# SeccionMicrocontrolador.net
KiCad netlist of a schematic drawn in Altium Designer
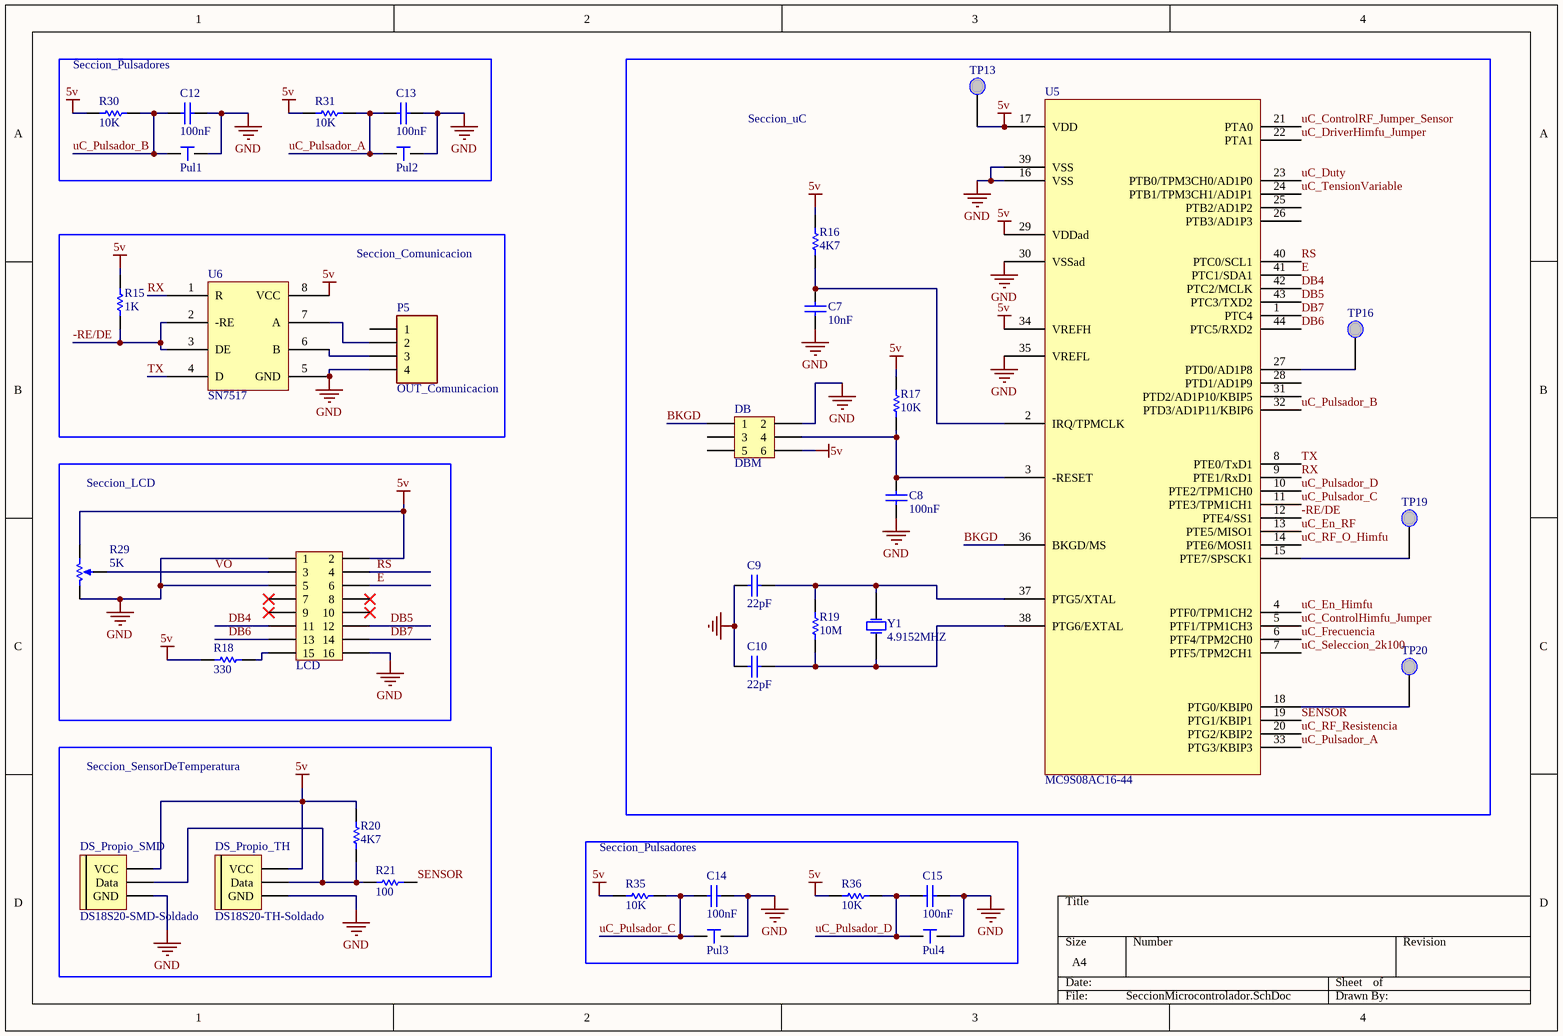
[diagram p0: SeccionMicrocontrolador.SchDoc]

(export (version "E")
  (design (tool "Eeschema 10.0.6"))
  (components
    (comp (ref "C7")
      (value "10nF")
      (footprint "Nahuel_SMD_Body:C_0805")
      (description "CAP CER 10000PF 25V X7R 0805")
      (fields (field (name "PUBLISHER") "Altium Limited"))
      (libsource (lib "Nahuel_SMD_Body") (part "C_10nF"))
    )
    (comp (ref "C8")
      (value "100nF")
      (footprint "Nahuel_SMD_Body:C_0805")
      (description "CAP CER 0.1UF 25V X7R 0805")
      (fields (field (name "PUBLISHER") "Altium Limited"))
      (libsource (lib "Nahuel_SMD_Body") (part "C_100nF"))
    )
    (comp (ref "C9")
      (value "22pF")
      (footprint "Nahuel_SMD_Body:C_0805")
      (description "CAP CER 22PF 50V C0G/NP0 0805")
      (fields (field (name "PUBLISHER") "Altium Limited"))
      (libsource (lib "Nahuel_SMD_Body") (part "C_22pF"))
    )
    (comp (ref "C10")
      (value "22pF")
      (footprint "Nahuel_SMD_Body:C_0805")
      (description "CAP CER 22PF 50V C0G/NP0 0805")
      (fields (field (name "PUBLISHER") "Altium Limited"))
      (libsource (lib "Nahuel_SMD_Body") (part "C_22pF"))
    )
    (comp (ref "C12")
      (value "100nF")
      (footprint "Nahuel_SMD_Body:C_0805")
      (description "CAP CER 0.1UF 25V X7R 0805")
      (fields (field (name "PUBLISHER") "Altium Limited"))
      (libsource (lib "Nahuel_SMD_Body") (part "C_100nF"))
    )
    (comp (ref "C13")
      (value "100nF")
      (footprint "Nahuel_SMD_Body:C_0805")
      (description "CAP CER 0.1UF 25V X7R 0805")
      (fields (field (name "PUBLISHER") "Altium Limited"))
      (libsource (lib "Nahuel_SMD_Body") (part "C_100nF"))
    )
    (comp (ref "C14")
      (value "100nF")
      (footprint "Nahuel_SMD_Body:C_0805")
      (description "CAP CER 0.1UF 25V X7R 0805")
      (fields (field (name "PUBLISHER") "Altium Limited"))
      (libsource (lib "Nahuel_SMD_Body") (part "C_100nF"))
    )
    (comp (ref "C15")
      (value "100nF")
      (footprint "Nahuel_SMD_Body:C_0805")
      (description "CAP CER 0.1UF 25V X7R 0805")
      (fields (field (name "PUBLISHER") "Altium Limited"))
      (libsource (lib "Nahuel_SMD_Body") (part "C_100nF"))
    )
    (comp (ref "DB")
      (value "DBM")
      (footprint "Nahuel_TH_BODY:DBM")
      (description "CONN HEADER VERT 6POS 2.54MM")
      (fields (field (name "PUBLISHER") "Altium Limited"))
      (libsource (lib "Nahuel_TH_BODY") (part "DBM"))
    )
    (comp (ref "DS_Propio_SMD")
      (value "DS18S20-SMD-Soldado")
      (footprint "Nahuel_SMD_Body:SOIC8")
      (description "SENSOR DIGITAL -55C-125C 8SOIC")
      (fields (field (name "PUBLISHER") "Altium Limited"))
      (libsource (lib "Nahuel_SMD_Body") (part "DS18S20-SMD-Soldado"))
    )
    (comp (ref "DS_Propio_TH")
      (value "DS18S20-TH-Soldado")
      (footprint "Nahuel_TH_BODY:TO92")
      (description "Temperature Sensor Digital, Local -55°C ~ 125°C 8 b TO-92-3")
      (fields (field (name "PUBLISHER") "Altium Limited"))
      (libsource (lib "Nahuel_TH_BODY") (part "DS18S20-TH-Soldado"))
    )
    (comp (ref "LCD")
      (value "LCD_Pines")
      (footprint "Nahuel_TH_BODY:LCD_Pines")
      (description "CONN HEADER VERT 16POS 2.54MM")
      (fields (field (name "PUBLISHER") "Altium Limited"))
      (libsource (lib "Nahuel_TH_BODY") (part "LCD_Pines"))
    )
    (comp (ref "P5")
      (value "OUT_Comunicacion")
      (footprint "B4B-XH-A_3D")
      (description "CONN HEADER XH TOP 4POS 2.5MM")
      (fields (field (name "PUBLISHER") "Altium Limited"))
      (libsource (lib "Nahuel_Connectors_BODY") (part "JST_2.5_4"))
    )
    (comp (ref "Pul1")
      (value "PinesParaPulsador")
      (footprint "Nahuel_TH_BODY:Jumper-Simple")
      (description "CONN HEADER 2 POS 2.54")
      (fields (field (name "PUBLISHER") "Altium Limited"))
      (libsource (lib "Nahuel_TH_BODY") (part "PinesParaPulsador"))
    )
    (comp (ref "Pul2")
      (value "PinesParaPulsador")
      (footprint "Nahuel_TH_BODY:Jumper-Simple")
      (description "CONN HEADER 2 POS 2.54")
      (fields (field (name "PUBLISHER") "Altium Limited"))
      (libsource (lib "Nahuel_TH_BODY") (part "PinesParaPulsador"))
    )
    (comp (ref "Pul3")
      (value "PinesParaPulsador")
      (footprint "Nahuel_TH_BODY:Jumper-Simple")
      (description "CONN HEADER 2 POS 2.54")
      (fields (field (name "PUBLISHER") "Altium Limited"))
      (libsource (lib "Nahuel_TH_BODY") (part "PinesParaPulsador"))
    )
    (comp (ref "Pul4")
      (value "PinesParaPulsador")
      (footprint "Nahuel_TH_BODY:Jumper-Simple")
      (description "CONN HEADER 2 POS 2.54")
      (fields (field (name "PUBLISHER") "Altium Limited"))
      (libsource (lib "Nahuel_TH_BODY") (part "PinesParaPulsador"))
    )
    (comp (ref "R15")
      (value "1K")
      (footprint "Nahuel_SMD_Body:R_0805")
      (description "RES SMD 1K OHM 1% 1/8W 0805")
      (fields (field (name "PUBLISHER") "Altium Limited"))
      (libsource (lib "Nahuel_SMD_Body") (part "R_1k"))
    )
    (comp (ref "R16")
      (value "4K7")
      (footprint "Nahuel_SMD_Body:R_0805")
      (description "RES SMD 4K7 OHM 1% 1/8W 0805")
      (fields (field (name "PUBLISHER") "Altium Limited"))
      (libsource (lib "Nahuel_SMD_Body") (part "R_4k7"))
    )
    (comp (ref "R17")
      (value "10K")
      (footprint "Nahuel_SMD_Body:R_0805")
      (description "RES SMD 10K OHM 1% 1/8W 0805")
      (fields (field (name "PUBLISHER") "Altium Limited"))
      (libsource (lib "Nahuel_SMD_Body") (part "R_10k"))
    )
    (comp (ref "R18")
      (value "330")
      (footprint "Nahuel_SMD_Body:R_0805")
      (description "RES SMD 330 OHM 1% 1/8W 0805")
      (fields (field (name "PUBLISHER") "Altium Limited"))
      (libsource (lib "Nahuel_SMD_Body") (part "R_330"))
    )
    (comp (ref "R19")
      (value "10M")
      (footprint "Nahuel_SMD_Body:R_0805")
      (description "RES SMD 10M OHM 5% 1/8W 0805")
      (fields (field (name "PUBLISHER") "Altium Limited"))
      (libsource (lib "Nahuel_SMD_Body") (part "R_10M"))
    )
    (comp (ref "R20")
      (value "4K7")
      (footprint "Nahuel_SMD_Body:R_0805")
      (description "RES SMD 4K7 OHM 1% 1/8W 0805")
      (fields (field (name "PUBLISHER") "Altium Limited"))
      (libsource (lib "Nahuel_SMD_Body") (part "R_4k7"))
    )
    (comp (ref "R21")
      (value "100")
      (footprint "Nahuel_SMD_Body:R_0805")
      (description "RES SMD 100 OHM 1% 1/8W 0805")
      (fields (field (name "PUBLISHER") "Altium Limited"))
      (libsource (lib "Nahuel_SMD_Body") (part "R_100"))
    )
    (comp (ref "R29")
      (value "5K")
      (footprint "Nahuel_SMD_Body:Preset_SMD")
      (description "TRIMMER 5K OHM 0.5W GW TOP ADJ")
      (fields (field (name "PUBLISHER") "Altium Limited"))
      (libsource (lib "Nahuel_SMD_Body") (part "Preset_5k_SMD"))
    )
    (comp (ref "R30")
      (value "10K")
      (footprint "Nahuel_SMD_Body:R_0805")
      (description "RES SMD 10K OHM 1% 1/8W 0805")
      (fields (field (name "PUBLISHER") "Altium Limited"))
      (libsource (lib "Nahuel_SMD_Body") (part "R_10k"))
    )
    (comp (ref "R31")
      (value "10K")
      (footprint "Nahuel_SMD_Body:R_0805")
      (description "RES SMD 10K OHM 1% 1/8W 0805")
      (fields (field (name "PUBLISHER") "Altium Limited"))
      (libsource (lib "Nahuel_SMD_Body") (part "R_10k"))
    )
    (comp (ref "R35")
      (value "10K")
      (footprint "Nahuel_SMD_Body:R_0805")
      (description "RES SMD 10K OHM 1% 1/8W 0805")
      (fields (field (name "PUBLISHER") "Altium Limited"))
      (libsource (lib "Nahuel_SMD_Body") (part "R_10k"))
    )
    (comp (ref "R36")
      (value "10K")
      (footprint "Nahuel_SMD_Body:R_0805")
      (description "RES SMD 10K OHM 1% 1/8W 0805")
      (fields (field (name "PUBLISHER") "Altium Limited"))
      (libsource (lib "Nahuel_SMD_Body") (part "R_10k"))
    )
    (comp (ref "TP13")
      (value "5V")
      (footprint "Nahuel_TH_BODY:TP-5002")
      (fields (field (name "PUBLISHER") "Altium Limited"))
      (libsource (lib "Nahuel_TH_BODY") (part "TestPoint"))
    )
    (comp (ref "TP16")
      (value "PTD0")
      (footprint "Nahuel_TH_BODY:TP-5002")
      (fields (field (name "PUBLISHER") "Altium Limited"))
      (libsource (lib "Nahuel_TH_BODY") (part "TestPoint"))
    )
    (comp (ref "TP19")
      (value "PTE7")
      (footprint "Nahuel_TH_BODY:TP-5002")
      (fields (field (name "PUBLISHER") "Altium Limited"))
      (libsource (lib "Nahuel_TH_BODY") (part "TestPoint"))
    )
    (comp (ref "TP20")
      (value "PTG0")
      (footprint "Nahuel_TH_BODY:TP-5002")
      (fields (field (name "PUBLISHER") "Altium Limited"))
      (libsource (lib "Nahuel_TH_BODY") (part "TestPoint"))
    )
    (comp (ref "U5")
      (value "MC9S08AC16-44")
      (footprint "Nahuel_SMD_Body:QFP10x10-G44/Z14.4N")
      (description "S08 S08 Microcontroller IC 8-Bit 40MHz 16KB (16K x 8) FLASH 32-LQFP (7x7)")
      (fields (field (name "PUBLISHER") "*"))
      (libsource (lib "Nahuel_SMD_Body") (part "MC9S08AC16-44"))
    )
    (comp (ref "U6")
      (value "SN7517")
      (footprint "Nahuel_SMD_Body:751-07_N")
      (description "IC TXRX DIFF BUSS 8SOIC")
      (fields (field (name "PUBLISHER") "Altium Limited"))
      (libsource (lib "Nahuel_SMD_Body") (part "SN7517"))
    )
    (comp (ref "Y1")
      (value "4.9152MHZ")
      (footprint "Nahuel_TH_BODY:XTAL_LOW")
      (description "CRYSTAL 4.9152MHZ 18PF T/H")
      (fields (field (name "PUBLISHER") "*"))
      (libsource (lib "Nahuel_TH_BODY") (part "XTAL_LOW"))
    )
  )
  (nets
    (net (code "1") (name "/-RE{slash}DE") (class "Default")
      (node (ref "R15") (pin "1") (pinfunction "1_1") (pintype "passive"))
      (node (ref "U5") (pin "12") (pinfunction "PTE4/SS1_12") (pintype "passive"))
      (node (ref "U6") (pin "2") (pinfunction "-RE_2") (pintype "passive"))
      (node (ref "U6") (pin "3") (pinfunction "DE_3") (pintype "passive"))
    )
    (net (code "2") (name "/BKGD") (class "Default")
      (node (ref "DB") (pin "1") (pinfunction "1_1") (pintype "passive"))
      (node (ref "U5") (pin "36") (pinfunction "BKGD/MS_36") (pintype "passive"))
    )
    (net (code "3") (name "/DB4") (class "Default")
      (node (ref "LCD") (pin "11") (pinfunction "11_11") (pintype "passive"))
      (node (ref "U5") (pin "42") (pinfunction "PTC2/MCLK_42") (pintype "passive"))
    )
    (net (code "4") (name "/DB5") (class "Default")
      (node (ref "LCD") (pin "12") (pinfunction "12_12") (pintype "passive"))
      (node (ref "U5") (pin "43") (pinfunction "PTC3/TXD2_43") (pintype "passive"))
    )
    (net (code "5") (name "/DB6") (class "Default")
      (node (ref "LCD") (pin "13") (pinfunction "13_13") (pintype "passive"))
      (node (ref "U5") (pin "44") (pinfunction "PTC5/RXD2_44") (pintype "passive"))
    )
    (net (code "6") (name "/DB7") (class "Default")
      (node (ref "LCD") (pin "14") (pinfunction "14_14") (pintype "passive"))
      (node (ref "U5") (pin "1") (pinfunction "PTC4_1") (pintype "passive"))
    )
    (net (code "7") (name "/E") (class "Default")
      (node (ref "LCD") (pin "6") (pinfunction "6_6") (pintype "passive"))
      (node (ref "U5") (pin "41") (pinfunction "PTC1/SDA1_41") (pintype "passive"))
    )
    (net (code "8") (name "/RS") (class "Default")
      (node (ref "LCD") (pin "4") (pinfunction "4_4") (pintype "passive"))
      (node (ref "U5") (pin "40") (pinfunction "PTC0/SCL1_40") (pintype "passive"))
    )
    (net (code "9") (name "/RX") (class "Default")
      (node (ref "U5") (pin "9") (pinfunction "PTE1/RxD1_9") (pintype "passive"))
      (node (ref "U6") (pin "1") (pinfunction "R_1") (pintype "passive"))
    )
    (net (code "10") (name "/SENSOR") (class "Default")
      (node (ref "R21") (pin "2") (pinfunction "2_2") (pintype "passive"))
      (node (ref "U5") (pin "19") (pinfunction "PTG1/KBIP1_19") (pintype "passive"))
    )
    (net (code "11") (name "/TX") (class "Default")
      (node (ref "U5") (pin "8") (pinfunction "PTE0/TxD1_8") (pintype "passive"))
      (node (ref "U6") (pin "4") (pinfunction "D_4") (pintype "passive"))
    )
    (net (code "12") (name "/VO") (class "Default")
      (node (ref "LCD") (pin "3") (pinfunction "3_3") (pintype "passive"))
      (node (ref "R29") (pin "2") (pinfunction "TAP_2") (pintype "passive"))
    )
    (net (code "13") (name "/uC_ControlHimfu_Jumper") (class "Default")
      (node (ref "U5") (pin "5") (pinfunction "PTF1/TPM1CH3_5") (pintype "passive"))
    )
    (net (code "14") (name "/uC_ControlRF_Jumper_Sensor") (class "Default")
      (node (ref "U5") (pin "21") (pinfunction "PTA0_21") (pintype "passive"))
    )
    (net (code "15") (name "/uC_DriverHimfu_Jumper") (class "Default")
      (node (ref "U5") (pin "22") (pinfunction "PTA1_22") (pintype "passive"))
    )
    (net (code "16") (name "/uC_Duty") (class "Default")
      (node (ref "U5") (pin "23") (pinfunction "PTB0/TPM3CH0/AD1P0_23") (pintype "passive"))
    )
    (net (code "17") (name "/uC_En_Himfu") (class "Default")
      (node (ref "U5") (pin "4") (pinfunction "PTF0/TPM1CH2_4") (pintype "passive"))
    )
    (net (code "18") (name "/uC_En_RF") (class "Default")
      (node (ref "U5") (pin "13") (pinfunction "PTE5/MISO1_13") (pintype "passive"))
    )
    (net (code "19") (name "/uC_Frecuencia") (class "Default")
      (node (ref "U5") (pin "6") (pinfunction "PTF4/TPM2CH0_6") (pintype "passive"))
    )
    (net (code "20") (name "/uC_Pulsador_A") (class "Default")
      (node (ref "C13") (pin "2") (pinfunction "2_2") (pintype "passive"))
      (node (ref "Pul2") (pin "2") (pinfunction "2_2") (pintype "passive"))
      (node (ref "R31") (pin "1") (pinfunction "1_1") (pintype "passive"))
      (node (ref "U5") (pin "33") (pinfunction "PTG3/KBIP3_33") (pintype "passive"))
    )
    (net (code "21") (name "/uC_Pulsador_B") (class "Default")
      (node (ref "C12") (pin "2") (pinfunction "2_2") (pintype "passive"))
      (node (ref "Pul1") (pin "2") (pinfunction "2_2") (pintype "passive"))
      (node (ref "R30") (pin "1") (pinfunction "1_1") (pintype "passive"))
      (node (ref "U5") (pin "32") (pinfunction "PTD3/AD1P11/KBIP6_32") (pintype "passive"))
    )
    (net (code "22") (name "/uC_Pulsador_C") (class "Default")
      (node (ref "C14") (pin "2") (pinfunction "2_2") (pintype "passive"))
      (node (ref "Pul3") (pin "2") (pinfunction "2_2") (pintype "passive"))
      (node (ref "R35") (pin "1") (pinfunction "1_1") (pintype "passive"))
      (node (ref "U5") (pin "11") (pinfunction "PTE3/TPM1CH1_11") (pintype "passive"))
    )
    (net (code "23") (name "/uC_Pulsador_D") (class "Default")
      (node (ref "C15") (pin "2") (pinfunction "2_2") (pintype "passive"))
      (node (ref "Pul4") (pin "2") (pinfunction "2_2") (pintype "passive"))
      (node (ref "R36") (pin "1") (pinfunction "1_1") (pintype "passive"))
      (node (ref "U5") (pin "10") (pinfunction "PTE2/TPM1CH0_10") (pintype "passive"))
    )
    (net (code "24") (name "/uC_RF_O_Himfu") (class "Default")
      (node (ref "U5") (pin "14") (pinfunction "PTE6/MOSI1_14") (pintype "passive"))
    )
    (net (code "25") (name "/uC_RF_Resistencia") (class "Default")
      (node (ref "U5") (pin "20") (pinfunction "PTG2/KBIP2_20") (pintype "passive"))
    )
    (net (code "26") (name "/uC_Seleccion_2k100") (class "Default")
      (node (ref "U5") (pin "7") (pinfunction "PTF5/TPM2CH1_7") (pintype "passive"))
    )
    (net (code "27") (name "/uC_TensionVariable") (class "Default")
      (node (ref "U5") (pin "24") (pinfunction "PTB1/TPM3CH1/AD1P1_24") (pintype "passive"))
    )
    (net (code "28") (name "5v") (class "Default")
      (node (ref "DB") (pin "6") (pinfunction "6_6") (pintype "passive"))
      (node (ref "DS_Propio_SMD") (pin "3") (pinfunction "VCC_3") (pintype "passive"))
      (node (ref "DS_Propio_TH") (pin "3") (pinfunction "VCC_3") (pintype "passive"))
      (node (ref "LCD") (pin "2") (pinfunction "2_2") (pintype "passive"))
      (node (ref "R15") (pin "2") (pinfunction "2_2") (pintype "passive"))
      (node (ref "R16") (pin "2") (pinfunction "2_2") (pintype "passive"))
      (node (ref "R17") (pin "2") (pinfunction "2_2") (pintype "passive"))
      (node (ref "R18") (pin "1") (pinfunction "1_1") (pintype "passive"))
      (node (ref "R20") (pin "2") (pinfunction "2_2") (pintype "passive"))
      (node (ref "R29") (pin "1") (pinfunction "TOP_CCW_1") (pintype "passive"))
      (node (ref "R30") (pin "2") (pinfunction "2_2") (pintype "passive"))
      (node (ref "R31") (pin "2") (pinfunction "2_2") (pintype "passive"))
      (node (ref "R35") (pin "2") (pinfunction "2_2") (pintype "passive"))
      (node (ref "R36") (pin "2") (pinfunction "2_2") (pintype "passive"))
      (node (ref "TP13") (pin "1") (pinfunction "1_1") (pintype "passive"))
      (node (ref "U5") (pin "17") (pinfunction "VDD_17") (pintype "passive"))
      (node (ref "U5") (pin "29") (pinfunction "VDDad_29") (pintype "passive"))
      (node (ref "U5") (pin "34") (pinfunction "VREFH_34") (pintype "passive"))
      (node (ref "U6") (pin "8") (pinfunction "VCC_8") (pintype "passive"))
    )
    (net (code "29") (name "GND") (class "Default")
      (node (ref "C10") (pin "1") (pinfunction "1_1") (pintype "passive"))
      (node (ref "C12") (pin "1") (pinfunction "1_1") (pintype "passive"))
      (node (ref "C13") (pin "1") (pinfunction "1_1") (pintype "passive"))
      (node (ref "C14") (pin "1") (pinfunction "1_1") (pintype "passive"))
      (node (ref "C15") (pin "1") (pinfunction "1_1") (pintype "passive"))
      (node (ref "C7") (pin "1") (pinfunction "1_1") (pintype "passive"))
      (node (ref "C8") (pin "1") (pinfunction "1_1") (pintype "passive"))
      (node (ref "C9") (pin "1") (pinfunction "1_1") (pintype "passive"))
      (node (ref "DB") (pin "2") (pinfunction "2_2") (pintype "passive"))
      (node (ref "DS_Propio_SMD") (pin "5") (pinfunction "GND_5") (pintype "passive"))
      (node (ref "DS_Propio_TH") (pin "1") (pinfunction "GND_1") (pintype "passive"))
      (node (ref "LCD") (pin "1") (pinfunction "1_1") (pintype "passive"))
      (node (ref "LCD") (pin "16") (pinfunction "16_16") (pintype "passive"))
      (node (ref "LCD") (pin "5") (pinfunction "5_5") (pintype "passive"))
      (node (ref "P5") (pin "4") (pinfunction "4_4") (pintype "passive"))
      (node (ref "Pul1") (pin "1") (pinfunction "1_1") (pintype "passive"))
      (node (ref "Pul2") (pin "1") (pinfunction "1_1") (pintype "passive"))
      (node (ref "Pul3") (pin "1") (pinfunction "1_1") (pintype "passive"))
      (node (ref "Pul4") (pin "1") (pinfunction "1_1") (pintype "passive"))
      (node (ref "R29") (pin "3") (pinfunction "BOT_CW_3") (pintype "passive"))
      (node (ref "U5") (pin "16") (pinfunction "VSS_16") (pintype "passive"))
      (node (ref "U5") (pin "30") (pinfunction "VSSad_30") (pintype "passive"))
      (node (ref "U5") (pin "35") (pinfunction "VREFL_35") (pintype "passive"))
      (node (ref "U5") (pin "39") (pinfunction "VSS_39") (pintype "passive"))
      (node (ref "U6") (pin "5") (pinfunction "GND_5") (pintype "passive"))
    )
    (net (code "30") (name "Net-(DS_Propio_SMD-Data)") (class "Default")
      (node (ref "DS_Propio_SMD") (pin "4") (pinfunction "Data_4") (pintype "passive"))
      (node (ref "DS_Propio_TH") (pin "2") (pinfunction "Data_2") (pintype "passive"))
      (node (ref "R20") (pin "1") (pinfunction "1_1") (pintype "passive"))
      (node (ref "R21") (pin "1") (pinfunction "1_1") (pintype "passive"))
    )
    (net (code "31") (name "Net-(LCD-Pad15)") (class "Default")
      (node (ref "LCD") (pin "15") (pinfunction "15_15") (pintype "passive"))
      (node (ref "R18") (pin "2") (pinfunction "2_2") (pintype "passive"))
    )
    (net (code "32") (name "Net-(U5--RESET)") (class "Default")
      (node (ref "C8") (pin "2") (pinfunction "2_2") (pintype "passive"))
      (node (ref "DB") (pin "4") (pinfunction "4_4") (pintype "passive"))
      (node (ref "R17") (pin "1") (pinfunction "1_1") (pintype "passive"))
      (node (ref "U5") (pin "3") (pinfunction "-RESET_3") (pintype "passive"))
    )
    (net (code "33") (name "Net-(U5-IRQ{slash}TPMCLK)") (class "Default")
      (node (ref "C7") (pin "2") (pinfunction "2_2") (pintype "passive"))
      (node (ref "R16") (pin "1") (pinfunction "1_1") (pintype "passive"))
      (node (ref "U5") (pin "2") (pinfunction "IRQ/TPMCLK_2") (pintype "passive"))
    )
    (net (code "34") (name "Net-(U5-PTD0{slash}AD1P8)") (class "Default")
      (node (ref "TP16") (pin "1") (pinfunction "1_1") (pintype "passive"))
      (node (ref "U5") (pin "27") (pinfunction "PTD0/AD1P8_27") (pintype "passive"))
    )
    (net (code "35") (name "Net-(U5-PTE7{slash}SPSCK1)") (class "Default")
      (node (ref "TP19") (pin "1") (pinfunction "1_1") (pintype "passive"))
      (node (ref "U5") (pin "15") (pinfunction "PTE7/SPSCK1_15") (pintype "passive"))
    )
    (net (code "36") (name "Net-(U5-PTG0{slash}KBIP0)") (class "Default")
      (node (ref "TP20") (pin "1") (pinfunction "1_1") (pintype "passive"))
      (node (ref "U5") (pin "18") (pinfunction "PTG0/KBIP0_18") (pintype "passive"))
    )
    (net (code "37") (name "Net-(U5-PTG5{slash}XTAL)") (class "Default")
      (node (ref "C9") (pin "2") (pinfunction "2_2") (pintype "passive"))
      (node (ref "R19") (pin "2") (pinfunction "2_2") (pintype "passive"))
      (node (ref "U5") (pin "37") (pinfunction "PTG5/XTAL_37") (pintype "passive"))
      (node (ref "Y1") (pin "2") (pinfunction "OSC2_2") (pintype "passive"))
    )
    (net (code "38") (name "Net-(U5-PTG6{slash}EXTAL)") (class "Default")
      (node (ref "C10") (pin "2") (pinfunction "2_2") (pintype "passive"))
      (node (ref "R19") (pin "1") (pinfunction "1_1") (pintype "passive"))
      (node (ref "U5") (pin "38") (pinfunction "PTG6/EXTAL_38") (pintype "passive"))
      (node (ref "Y1") (pin "1") (pinfunction "OSC1_1") (pintype "passive"))
    )
    (net (code "39") (name "Net-(U6-A)") (class "Default")
      (node (ref "P5") (pin "2") (pinfunction "2_2") (pintype "passive"))
      (node (ref "U6") (pin "7") (pinfunction "A_7") (pintype "passive"))
    )
    (net (code "40") (name "Net-(U6-B)") (class "Default")
      (node (ref "P5") (pin "3") (pinfunction "3_3") (pintype "passive"))
      (node (ref "U6") (pin "6") (pinfunction "B_6") (pintype "passive"))
    )
    (net (code "41") (name "unconnected-(DB-Pad3)") (class "Default")
      (node (ref "DB") (pin "3") (pinfunction "3_3") (pintype "passive"))
    )
    (net (code "42") (name "unconnected-(DB-Pad5)") (class "Default")
      (node (ref "DB") (pin "5") (pinfunction "5_5") (pintype "passive"))
    )
    (net (code "43") (name "unconnected-(LCD-Pad7)") (class "Default")
      (node (ref "LCD") (pin "7") (pinfunction "7_7") (pintype "passive+no_connect"))
    )
    (net (code "44") (name "unconnected-(LCD-Pad8)") (class "Default")
      (node (ref "LCD") (pin "8") (pinfunction "8_8") (pintype "passive+no_connect"))
    )
    (net (code "45") (name "unconnected-(LCD-Pad9)") (class "Default")
      (node (ref "LCD") (pin "9") (pinfunction "9_9") (pintype "passive+no_connect"))
    )
    (net (code "46") (name "unconnected-(LCD-Pad10)") (class "Default")
      (node (ref "LCD") (pin "10") (pinfunction "10_10") (pintype "passive+no_connect"))
    )
    (net (code "47") (name "unconnected-(P5-Pad1)") (class "Default")
      (node (ref "P5") (pin "1") (pinfunction "1_1") (pintype "passive"))
    )
    (net (code "48") (name "unconnected-(U5-PTB2{slash}AD1P2-Pad25)") (class "Default")
      (node (ref "U5") (pin "25") (pinfunction "PTB2/AD1P2_25") (pintype "passive"))
    )
    (net (code "49") (name "unconnected-(U5-PTB3{slash}AD1P3-Pad26)") (class "Default")
      (node (ref "U5") (pin "26") (pinfunction "PTB3/AD1P3_26") (pintype "passive"))
    )
    (net (code "50") (name "unconnected-(U5-PTD1{slash}AD1P9-Pad28)") (class "Default")
      (node (ref "U5") (pin "28") (pinfunction "PTD1/AD1P9_28") (pintype "passive"))
    )
    (net (code "51") (name "unconnected-(U5-PTD2{slash}AD1P10{slash}KBIP5-Pad31)") (class "Default")
      (node (ref "U5") (pin "31") (pinfunction "PTD2/AD1P10/KBIP5_31") (pintype "passive"))
    )
  )
)
